# HLK-W806-KIT-V1_2.net
KiCad netlist of a schematic drawn in Altium Designer
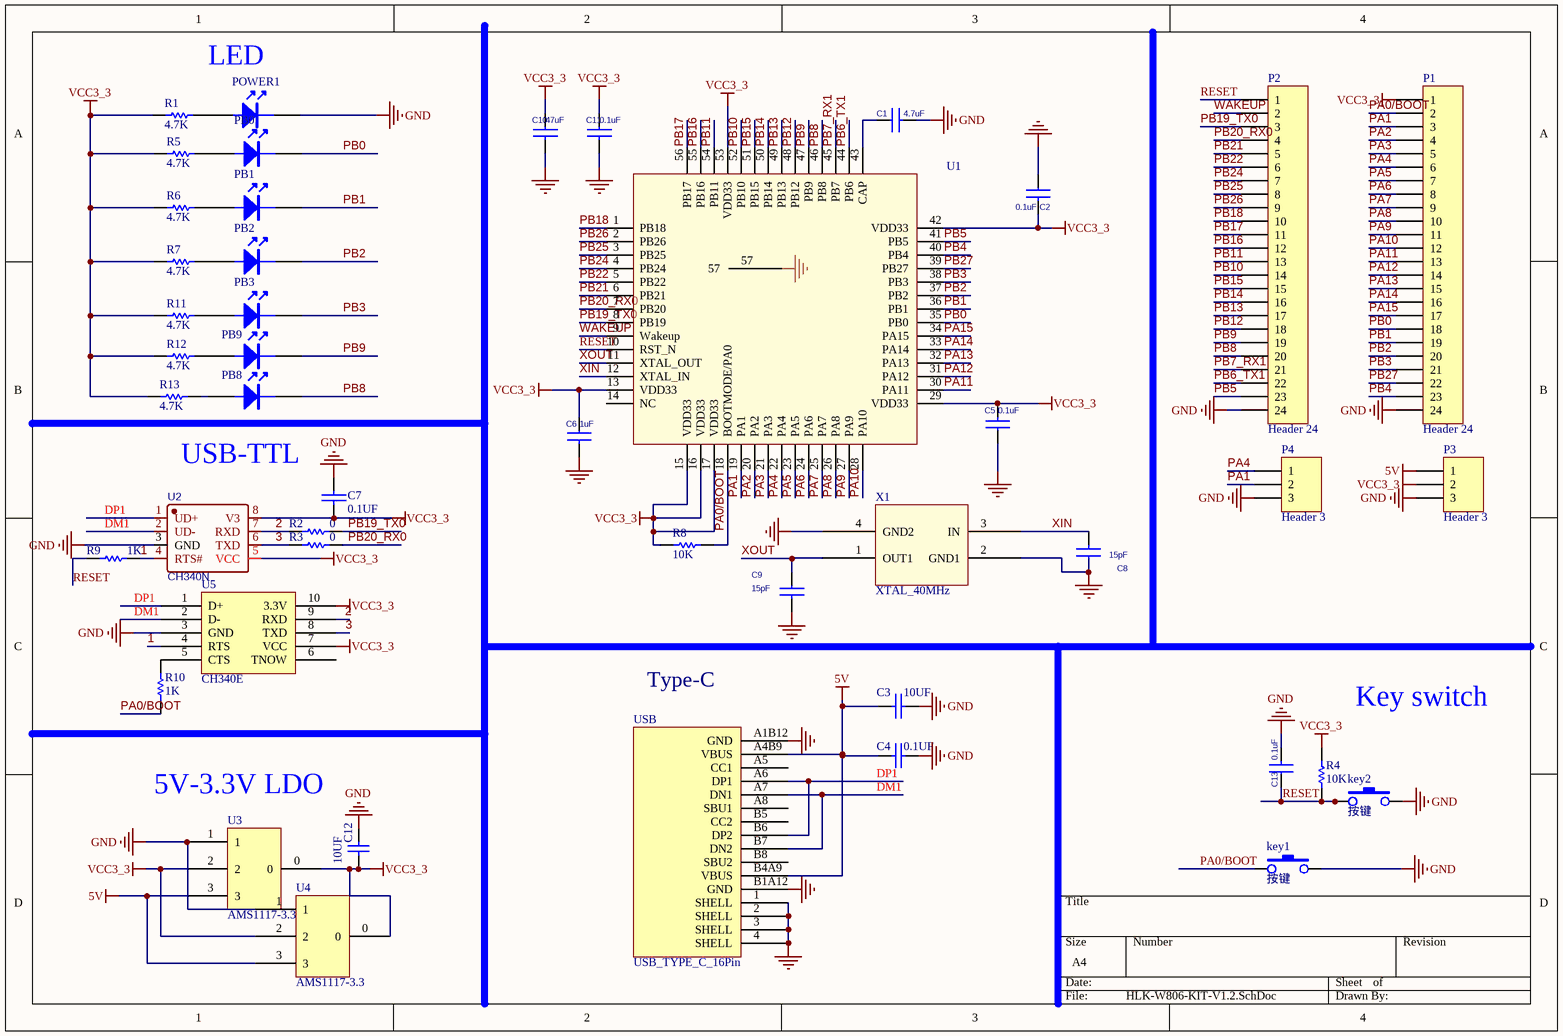
[diagram p0: HLK-W806-KIT-V1.2.SchDoc]

(export (version "E")
  (design (tool "Eeschema 10.0.6"))
  (components
    (comp (ref "C1") (value "4.7uF") (footprint "0603") (libsource (lib "*") (part "CAP NP_Dup1")))
    (comp (ref "C2") (value "0.1uF") (footprint "0603") (libsource (lib "*") (part "CAP NP_Dup1")))
    (comp (ref "C3")
      (value "10UF")
      (footprint "0603_1")
      (description "Capacitor")
      (libsource (lib "*") (part "CAP"))
    )
    (comp (ref "C4")
      (value "0.1UF")
      (footprint "0603_1")
      (description "Capacitor")
      (libsource (lib "*") (part "CAP"))
    )
    (comp (ref "C5") (value "0.1uF") (footprint "0603") (libsource (lib "*") (part "CAP NP_Dup1")))
    (comp (ref "C6") (value "1uF") (footprint "0603") (libsource (lib "*") (part "CAP NP_Dup1")))
    (comp (ref "C7")
      (value "0.1UF")
      (footprint "0603_1")
      (description "Capacitor")
      (libsource (lib "*") (part "CAP"))
    )
    (comp (ref "C8") (value "15pF") (footprint "0603") (libsource (lib "*") (part "CAP NP_Dup1")))
    (comp (ref "C9") (value "15pF") (footprint "0603") (libsource (lib "*") (part "CAP NP_Dup1")))
    (comp (ref "C10") (value "47uF") (footprint "R0805") (libsource (lib "*") (part "CAP NP_Dup1")))
    (comp (ref "C11") (value "0.1uF") (footprint "0603") (libsource (lib "*") (part "CAP NP_Dup1")))
    (comp (ref "C12")
      (value "10UF")
      (footprint "0603_1")
      (description "Capacitor")
      (fields (field (name "PUBLISHER") "Altium Limited"))
      (libsource (lib "Miscellaneous Devices") (part "Cap"))
    )
    (comp (ref "C13") (value "0.1uF") (footprint "0603") (libsource (lib "*") (part "CAP NP_Dup1")))
    (comp (ref "key1") (value "按键") (footprint "正按小龟") (libsource (lib "标准通用原理图库") (part "按键")))
    (comp (ref "key2") (value "按键") (footprint "正按小龟") (libsource (lib "标准通用原理图库") (part "按键")))
    (comp (ref "P1")
      (value "Header 24")
      (footprint "HDR1X24")
      (description "Header, 24-Pin")
      (fields (field (name "PUBLISHER") "Altium Limited"))
      (libsource (lib "Miscellaneous Connectors") (part "Header 24"))
    )
    (comp (ref "P2")
      (value "Header 24")
      (footprint "HDR1X24")
      (description "Header, 24-Pin")
      (fields (field (name "PUBLISHER") "Altium Limited"))
      (libsource (lib "Miscellaneous Connectors") (part "Header 24"))
    )
    (comp (ref "P3")
      (value "Header 3")
      (footprint "HDR1X3")
      (description "Header, 3-Pin")
      (fields (field (name "PUBLISHER") "Altium Limited"))
      (libsource (lib "Miscellaneous Connectors") (part "Header 3"))
    )
    (comp (ref "P4")
      (value "Header 3")
      (footprint "HDR1X3")
      (description "Header, 3-Pin")
      (fields (field (name "PUBLISHER") "Altium Limited"))
      (libsource (lib "Miscellaneous Connectors") (part "Header 3"))
    )
    (comp (ref "PB0")
      (value "~")
      (footprint "0603LED")
      (libsource (lib "Miscellaneous Devices") (part "LED"))
    )
    (comp (ref "PB1")
      (value "~")
      (footprint "0603LED")
      (libsource (lib "Miscellaneous Devices") (part "LED"))
    )
    (comp (ref "PB2")
      (value "~")
      (footprint "0603LED")
      (libsource (lib "Miscellaneous Devices") (part "LED"))
    )
    (comp (ref "PB3")
      (value "~")
      (footprint "0603LED")
      (libsource (lib "Miscellaneous Devices") (part "LED"))
    )
    (comp (ref "PB8")
      (value "~")
      (footprint "0603LED")
      (libsource (lib "Miscellaneous Devices") (part "LED"))
    )
    (comp (ref "PB9")
      (value "~")
      (footprint "0603LED")
      (libsource (lib "Miscellaneous Devices") (part "LED"))
    )
    (comp (ref "POWER1")
      (value "~")
      (footprint "0603LED")
      (libsource (lib "Miscellaneous Devices") (part "LED"))
    )
    (comp (ref "R1")
      (value "4.7K")
      (footprint "0603_1")
      (description "Resistor")
      (fields (field (name "PUBLISHER") "Altium Limited"))
      (libsource (lib "Miscellaneous Devices") (part "Res1"))
    )
    (comp (ref "R2")
      (value "0")
      (footprint "0603_1")
      (description "Resistor")
      (fields (field (name "PUBLISHER") "Altium Limited"))
      (libsource (lib "Miscellaneous Devices") (part "Res1"))
    )
    (comp (ref "R3")
      (value "0")
      (footprint "0603_1")
      (description "Resistor")
      (fields (field (name "PUBLISHER") "Altium Limited"))
      (libsource (lib "Miscellaneous Devices") (part "Res1"))
    )
    (comp (ref "R4")
      (value "10K")
      (footprint "0603_1")
      (description "Resistor")
      (fields (field (name "PUBLISHER") "Altium Limited"))
      (libsource (lib "Miscellaneous Devices") (part "Res1"))
    )
    (comp (ref "R5")
      (value "4.7K")
      (footprint "0603_1")
      (description "Resistor")
      (fields (field (name "PUBLISHER") "Altium Limited"))
      (libsource (lib "Miscellaneous Devices") (part "Res1"))
    )
    (comp (ref "R6")
      (value "4.7K")
      (footprint "0603_1")
      (description "Resistor")
      (fields (field (name "PUBLISHER") "Altium Limited"))
      (libsource (lib "Miscellaneous Devices") (part "Res1"))
    )
    (comp (ref "R7")
      (value "4.7K")
      (footprint "0603_1")
      (description "Resistor")
      (fields (field (name "PUBLISHER") "Altium Limited"))
      (libsource (lib "Miscellaneous Devices") (part "Res1"))
    )
    (comp (ref "R8")
      (value "10K")
      (footprint "0603_1")
      (description "Resistor")
      (fields (field (name "PUBLISHER") "Altium Limited"))
      (libsource (lib "Miscellaneous Devices") (part "Res1"))
    )
    (comp (ref "R9")
      (value "1K")
      (footprint "0603_1")
      (description "Resistor")
      (fields (field (name "PUBLISHER") "Altium Limited"))
      (libsource (lib "Miscellaneous Devices") (part "Res1"))
    )
    (comp (ref "R10")
      (value "1K")
      (footprint "R 0603_L")
      (description "Resistor")
      (fields (field (name "PUBLISHER") "Altium Limited"))
      (libsource (lib "Miscellaneous Devices") (part "Res1"))
    )
    (comp (ref "R11")
      (value "4.7K")
      (footprint "0603_1")
      (description "Resistor")
      (fields (field (name "PUBLISHER") "Altium Limited"))
      (libsource (lib "Miscellaneous Devices") (part "Res1"))
    )
    (comp (ref "R12")
      (value "4.7K")
      (footprint "0603_1")
      (description "Resistor")
      (fields (field (name "PUBLISHER") "Altium Limited"))
      (libsource (lib "Miscellaneous Devices") (part "Res1"))
    )
    (comp (ref "R13")
      (value "4.7K")
      (footprint "0603_1")
      (description "Resistor")
      (fields (field (name "PUBLISHER") "Altium Limited"))
      (libsource (lib "Miscellaneous Devices") (part "Res1"))
    )
    (comp (ref "U1")
      (value "Component_1")
      (footprint "QFN-56")
      (libsource (lib "Schlib") (part "Component_1"))
    )
    (comp (ref "U2")
      (value "CH340N")
      (footprint "SOP8")
      (fields (field (name "BOM_SUPPLIER PART") "C506813") (field (name "CONTRIBUTOR") "LCSC"))
      (libsource (lib "Schlib1") (part "CH340N"))
    )
    (comp (ref "U3")
      (value "AMS1117-3.3")
      (footprint "AMS1117")
      (libsource (lib "Schlib1") (part "Component_1"))
    )
    (comp (ref "U4")
      (value "AMS1117-3.3")
      (footprint "SOT223")
      (libsource (lib "Schlib1") (part "Component_1"))
    )
    (comp (ref "U5") (value "CH340E") (footprint "MSOP10_L") (libsource (lib "Schlib1") (part "CH340E")))
    (comp (ref "USB")
      (value "USB_TYPE_C_16Pin")
      (footprint "USB-C-16PIN-1")
      (libsource (lib "Interface") (part "USB_TYPE_C_16Pin"))
    )
    (comp (ref "X1")
      (value "XTAL_40MHz")
      (footprint "SMD-3225")
      (libsource (lib "Schlib1") (part "XTAL_40MHz"))
    )
  )
  (nets
    (net (code "1") (name "/1") (class "Default")
      (node (ref "R9") (pin "2") (pinfunction "2_2") (pintype "passive"))
      (node (ref "U2") (pin "4") (pinfunction "RTS#_4") (pintype "passive"))
      (node (ref "U5") (pin "4") (pinfunction "RTS_4") (pintype "passive"))
    )
    (net (code "2") (name "/2") (class "Default")
      (node (ref "R2") (pin "1") (pinfunction "1_1") (pintype "passive"))
      (node (ref "U2") (pin "7") (pinfunction "RXD_7") (pintype "passive"))
      (node (ref "U5") (pin "9") (pinfunction "RXD_9") (pintype "passive"))
    )
    (net (code "3") (name "/3") (class "Default")
      (node (ref "R3") (pin "1") (pinfunction "1_1") (pintype "passive"))
      (node (ref "U2") (pin "6") (pinfunction "TXD_6") (pintype "passive"))
      (node (ref "U5") (pin "8") (pinfunction "TXD_8") (pintype "passive"))
    )
    (net (code "4") (name "/DM1") (class "Default")
      (node (ref "U2") (pin "2") (pinfunction "UD-_2") (pintype "passive"))
      (node (ref "U5") (pin "2") (pinfunction "D-_2") (pintype "passive"))
      (node (ref "USB") (pin "A7") (pinfunction "DN1_A7") (pintype "passive"))
      (node (ref "USB") (pin "B7") (pinfunction "DN2_B7") (pintype "passive"))
    )
    (net (code "5") (name "/DP1") (class "Default")
      (node (ref "U2") (pin "1") (pinfunction "UD+_1") (pintype "passive"))
      (node (ref "U5") (pin "1") (pinfunction "D+_1") (pintype "passive"))
      (node (ref "USB") (pin "A6") (pinfunction "DP1_A6") (pintype "passive"))
      (node (ref "USB") (pin "B6") (pinfunction "DP2_B6") (pintype "passive"))
    )
    (net (code "6") (name "/PA0{slash}BOOT") (class "Default")
      (node (ref "P1") (pin "2") (pinfunction "2_2") (pintype "passive"))
      (node (ref "R10") (pin "1") (pinfunction "1_1") (pintype "passive"))
      (node (ref "R8") (pin "2") (pinfunction "2_2") (pintype "passive"))
      (node (ref "U1") (pin "18") (pinfunction "BOOTMODE/PA0_18") (pintype "passive"))
      (node (ref "key1") (pin "1") (pinfunction "1_1") (pintype "passive"))
    )
    (net (code "7") (name "/PA1") (class "Default")
      (node (ref "P1") (pin "3") (pinfunction "3_3") (pintype "passive"))
      (node (ref "P4") (pin "2") (pinfunction "2_2") (pintype "passive"))
      (node (ref "U1") (pin "19") (pinfunction "PA1_19") (pintype "passive"))
    )
    (net (code "8") (name "/PA2") (class "Default")
      (node (ref "P1") (pin "4") (pinfunction "4_4") (pintype "passive"))
      (node (ref "U1") (pin "20") (pinfunction "PA2_20") (pintype "passive"))
    )
    (net (code "9") (name "/PA3") (class "Default")
      (node (ref "P1") (pin "5") (pinfunction "5_5") (pintype "passive"))
      (node (ref "U1") (pin "21") (pinfunction "PA3_21") (pintype "passive"))
    )
    (net (code "10") (name "/PA4") (class "Default")
      (node (ref "P1") (pin "6") (pinfunction "6_6") (pintype "passive"))
      (node (ref "P4") (pin "1") (pinfunction "1_1") (pintype "passive"))
      (node (ref "U1") (pin "22") (pinfunction "PA4_22") (pintype "passive"))
    )
    (net (code "11") (name "/PA5") (class "Default")
      (node (ref "P1") (pin "7") (pinfunction "7_7") (pintype "passive"))
      (node (ref "U1") (pin "23") (pinfunction "PA5_23") (pintype "passive"))
    )
    (net (code "12") (name "/PA6") (class "Default")
      (node (ref "P1") (pin "8") (pinfunction "8_8") (pintype "passive"))
      (node (ref "U1") (pin "24") (pinfunction "PA6_24") (pintype "passive"))
    )
    (net (code "13") (name "/PA7") (class "Default")
      (node (ref "P1") (pin "9") (pinfunction "9_9") (pintype "passive"))
      (node (ref "U1") (pin "25") (pinfunction "PA7_25") (pintype "passive"))
    )
    (net (code "14") (name "/PA8") (class "Default")
      (node (ref "P1") (pin "10") (pinfunction "10_10") (pintype "passive"))
      (node (ref "U1") (pin "26") (pinfunction "PA8_26") (pintype "passive"))
    )
    (net (code "15") (name "/PA9") (class "Default")
      (node (ref "P1") (pin "11") (pinfunction "11_11") (pintype "passive"))
      (node (ref "U1") (pin "27") (pinfunction "PA9_27") (pintype "passive"))
    )
    (net (code "16") (name "/PA10") (class "Default")
      (node (ref "P1") (pin "12") (pinfunction "12_12") (pintype "passive"))
      (node (ref "U1") (pin "28") (pinfunction "PA10_28") (pintype "passive"))
    )
    (net (code "17") (name "/PA11") (class "Default")
      (node (ref "P1") (pin "13") (pinfunction "13_13") (pintype "passive"))
      (node (ref "U1") (pin "30") (pinfunction "PA11_30") (pintype "passive"))
    )
    (net (code "18") (name "/PA12") (class "Default")
      (node (ref "P1") (pin "14") (pinfunction "14_14") (pintype "passive"))
      (node (ref "U1") (pin "31") (pinfunction "PA12_31") (pintype "passive"))
    )
    (net (code "19") (name "/PA13") (class "Default")
      (node (ref "P1") (pin "15") (pinfunction "15_15") (pintype "passive"))
      (node (ref "U1") (pin "32") (pinfunction "PA13_32") (pintype "passive"))
    )
    (net (code "20") (name "/PA14") (class "Default")
      (node (ref "P1") (pin "16") (pinfunction "16_16") (pintype "passive"))
      (node (ref "U1") (pin "33") (pinfunction "PA14_33") (pintype "passive"))
    )
    (net (code "21") (name "/PA15") (class "Default")
      (node (ref "P1") (pin "17") (pinfunction "17_17") (pintype "passive"))
      (node (ref "U1") (pin "34") (pinfunction "PA15_34") (pintype "passive"))
    )
    (net (code "22") (name "/PB0") (class "Default")
      (node (ref "P1") (pin "18") (pinfunction "18_18") (pintype "passive"))
      (node (ref "PB0") (pin "2") (pinfunction "2_2") (pintype "passive"))
      (node (ref "U1") (pin "35") (pinfunction "PB0_35") (pintype "passive"))
    )
    (net (code "23") (name "/PB1") (class "Default")
      (node (ref "P1") (pin "19") (pinfunction "19_19") (pintype "passive"))
      (node (ref "PB1") (pin "2") (pinfunction "2_2") (pintype "passive"))
      (node (ref "U1") (pin "36") (pinfunction "PB1_36") (pintype "passive"))
    )
    (net (code "24") (name "/PB2") (class "Default")
      (node (ref "P1") (pin "20") (pinfunction "20_20") (pintype "passive"))
      (node (ref "PB2") (pin "2") (pinfunction "2_2") (pintype "passive"))
      (node (ref "U1") (pin "37") (pinfunction "PB2_37") (pintype "passive"))
    )
    (net (code "25") (name "/PB3") (class "Default")
      (node (ref "P1") (pin "21") (pinfunction "21_21") (pintype "passive"))
      (node (ref "PB3") (pin "2") (pinfunction "2_2") (pintype "passive"))
      (node (ref "U1") (pin "38") (pinfunction "PB3_38") (pintype "passive"))
    )
    (net (code "26") (name "/PB4") (class "Default")
      (node (ref "P1") (pin "23") (pinfunction "23_23") (pintype "passive"))
      (node (ref "U1") (pin "40") (pinfunction "PB4_40") (pintype "passive"))
    )
    (net (code "27") (name "/PB5") (class "Default")
      (node (ref "P2") (pin "23") (pinfunction "23_23") (pintype "passive"))
      (node (ref "U1") (pin "41") (pinfunction "PB5_41") (pintype "passive"))
    )
    (net (code "28") (name "/PB6_TX1") (class "Default")
      (node (ref "P2") (pin "22") (pinfunction "22_22") (pintype "passive"))
      (node (ref "U1") (pin "44") (pinfunction "PB6_44") (pintype "passive"))
    )
    (net (code "29") (name "/PB7_RX1") (class "Default")
      (node (ref "P2") (pin "21") (pinfunction "21_21") (pintype "passive"))
      (node (ref "U1") (pin "45") (pinfunction "PB7_45") (pintype "passive"))
    )
    (net (code "30") (name "/PB8") (class "Default")
      (node (ref "P2") (pin "20") (pinfunction "20_20") (pintype "passive"))
      (node (ref "PB8") (pin "2") (pinfunction "2_2") (pintype "passive"))
      (node (ref "U1") (pin "46") (pinfunction "PB8_46") (pintype "passive"))
    )
    (net (code "31") (name "/PB9") (class "Default")
      (node (ref "P2") (pin "19") (pinfunction "19_19") (pintype "passive"))
      (node (ref "PB9") (pin "2") (pinfunction "2_2") (pintype "passive"))
      (node (ref "U1") (pin "47") (pinfunction "PB9_47") (pintype "passive"))
    )
    (net (code "32") (name "/PB10") (class "Default")
      (node (ref "P2") (pin "14") (pinfunction "14_14") (pintype "passive"))
      (node (ref "U1") (pin "52") (pinfunction "PB10_52") (pintype "passive"))
    )
    (net (code "33") (name "/PB11") (class "Default")
      (node (ref "P2") (pin "13") (pinfunction "13_13") (pintype "passive"))
      (node (ref "U1") (pin "54") (pinfunction "PB11_54") (pintype "passive"))
    )
    (net (code "34") (name "/PB12") (class "Default")
      (node (ref "P2") (pin "18") (pinfunction "18_18") (pintype "passive"))
      (node (ref "U1") (pin "48") (pinfunction "PB12_48") (pintype "passive"))
    )
    (net (code "35") (name "/PB13") (class "Default")
      (node (ref "P2") (pin "17") (pinfunction "17_17") (pintype "passive"))
      (node (ref "U1") (pin "49") (pinfunction "PB13_49") (pintype "passive"))
    )
    (net (code "36") (name "/PB14") (class "Default")
      (node (ref "P2") (pin "16") (pinfunction "16_16") (pintype "passive"))
      (node (ref "U1") (pin "50") (pinfunction "PB14_50") (pintype "passive"))
    )
    (net (code "37") (name "/PB15") (class "Default")
      (node (ref "P2") (pin "15") (pinfunction "15_15") (pintype "passive"))
      (node (ref "U1") (pin "51") (pinfunction "PB15_51") (pintype "passive"))
    )
    (net (code "38") (name "/PB16") (class "Default")
      (node (ref "P2") (pin "12") (pinfunction "12_12") (pintype "passive"))
      (node (ref "U1") (pin "55") (pinfunction "PB16_55") (pintype "passive"))
    )
    (net (code "39") (name "/PB17") (class "Default")
      (node (ref "P2") (pin "11") (pinfunction "11_11") (pintype "passive"))
      (node (ref "U1") (pin "56") (pinfunction "PB17_56") (pintype "passive"))
    )
    (net (code "40") (name "/PB18") (class "Default")
      (node (ref "P2") (pin "10") (pinfunction "10_10") (pintype "passive"))
      (node (ref "U1") (pin "1") (pinfunction "PB18_1") (pintype "passive"))
    )
    (net (code "41") (name "/PB19_TX0") (class "Default")
      (node (ref "P2") (pin "3") (pinfunction "3_3") (pintype "passive"))
      (node (ref "R2") (pin "2") (pinfunction "2_2") (pintype "passive"))
      (node (ref "U1") (pin "8") (pinfunction "PB19_8") (pintype "passive"))
    )
    (net (code "42") (name "/PB20_RX0") (class "Default")
      (node (ref "P2") (pin "4") (pinfunction "4_4") (pintype "passive"))
      (node (ref "R3") (pin "2") (pinfunction "2_2") (pintype "passive"))
      (node (ref "U1") (pin "7") (pinfunction "PB20_7") (pintype "passive"))
    )
    (net (code "43") (name "/PB21") (class "Default")
      (node (ref "P2") (pin "5") (pinfunction "5_5") (pintype "passive"))
      (node (ref "U1") (pin "6") (pinfunction "PB21_6") (pintype "passive"))
    )
    (net (code "44") (name "/PB22") (class "Default")
      (node (ref "P2") (pin "6") (pinfunction "6_6") (pintype "passive"))
      (node (ref "U1") (pin "5") (pinfunction "PB22_5") (pintype "passive"))
    )
    (net (code "45") (name "/PB24") (class "Default")
      (node (ref "P2") (pin "7") (pinfunction "7_7") (pintype "passive"))
      (node (ref "U1") (pin "4") (pinfunction "PB24_4") (pintype "passive"))
    )
    (net (code "46") (name "/PB25") (class "Default")
      (node (ref "P2") (pin "8") (pinfunction "8_8") (pintype "passive"))
      (node (ref "U1") (pin "3") (pinfunction "PB25_3") (pintype "passive"))
    )
    (net (code "47") (name "/PB26") (class "Default")
      (node (ref "P2") (pin "9") (pinfunction "9_9") (pintype "passive"))
      (node (ref "U1") (pin "2") (pinfunction "PB26_2") (pintype "passive"))
    )
    (net (code "48") (name "/PB27") (class "Default")
      (node (ref "P1") (pin "22") (pinfunction "22_22") (pintype "passive"))
      (node (ref "U1") (pin "39") (pinfunction "PB27_39") (pintype "passive"))
    )
    (net (code "49") (name "/RESET") (class "Default")
      (node (ref "C13") (pin "1") (pinfunction "1_1") (pintype "passive"))
      (node (ref "P2") (pin "1") (pinfunction "1_1") (pintype "passive"))
      (node (ref "R4") (pin "1") (pinfunction "1_1") (pintype "passive"))
      (node (ref "R9") (pin "1") (pinfunction "1_1") (pintype "passive"))
      (node (ref "U1") (pin "10") (pinfunction "RST_N_10") (pintype "passive"))
      (node (ref "key2") (pin "1") (pinfunction "1_1") (pintype "passive"))
    )
    (net (code "50") (name "/WAKEUP") (class "Default")
      (node (ref "P2") (pin "2") (pinfunction "2_2") (pintype "passive"))
      (node (ref "U1") (pin "9") (pinfunction "Wakeup_9") (pintype "passive"))
    )
    (net (code "51") (name "/XIN") (class "Default")
      (node (ref "C8") (pin "2") (pinfunction "2_2") (pintype "passive"))
      (node (ref "U1") (pin "12") (pinfunction "XTAL_IN_12") (pintype "passive"))
      (node (ref "X1") (pin "3") (pinfunction "IN_3") (pintype "passive"))
    )
    (net (code "52") (name "/XOUT") (class "Default")
      (node (ref "C9") (pin "1") (pinfunction "1_1") (pintype "passive"))
      (node (ref "U1") (pin "11") (pinfunction "XTAL_OUT_11") (pintype "passive"))
      (node (ref "X1") (pin "1") (pinfunction "OUT1_1") (pintype "passive"))
    )
    (net (code "53") (name "5V") (class "Default")
      (node (ref "C3") (pin "2") (pinfunction "2_2") (pintype "passive"))
      (node (ref "C4") (pin "2") (pinfunction "2_2") (pintype "passive"))
      (node (ref "P3") (pin "1") (pinfunction "1_1") (pintype "passive"))
      (node (ref "U3") (pin "3") (pinfunction "3_3") (pintype "passive"))
      (node (ref "U4") (pin "3") (pinfunction "3_3") (pintype "passive"))
      (node (ref "USB") (pin "A4B9") (pinfunction "VBUS_A4B9") (pintype "passive"))
      (node (ref "USB") (pin "B4A9") (pinfunction "VBUS_B4A9") (pintype "passive"))
    )
    (net (code "54") (name "GND") (class "Default")
      (node (ref "C1") (pin "2") (pinfunction "2_2") (pintype "passive"))
      (node (ref "C10") (pin "2") (pinfunction "2_2") (pintype "passive"))
      (node (ref "C11") (pin "2") (pinfunction "2_2") (pintype "passive"))
      (node (ref "C12") (pin "1") (pinfunction "1_1") (pintype "passive"))
      (node (ref "C13") (pin "2") (pinfunction "2_2") (pintype "passive"))
      (node (ref "C2") (pin "1") (pinfunction "1_1") (pintype "passive"))
      (node (ref "C3") (pin "1") (pinfunction "1_1") (pintype "passive"))
      (node (ref "C4") (pin "1") (pinfunction "1_1") (pintype "passive"))
      (node (ref "C5") (pin "1") (pinfunction "1_1") (pintype "passive"))
      (node (ref "C6") (pin "2") (pinfunction "2_2") (pintype "passive"))
      (node (ref "C7") (pin "1") (pinfunction "1_1") (pintype "passive"))
      (node (ref "C8") (pin "1") (pinfunction "1_1") (pintype "passive"))
      (node (ref "C9") (pin "2") (pinfunction "2_2") (pintype "passive"))
      (node (ref "P1") (pin "24") (pinfunction "24_24") (pintype "passive"))
      (node (ref "P2") (pin "24") (pinfunction "24_24") (pintype "passive"))
      (node (ref "P3") (pin "3") (pinfunction "3_3") (pintype "passive"))
      (node (ref "P4") (pin "3") (pinfunction "3_3") (pintype "passive"))
      (node (ref "POWER1") (pin "2") (pinfunction "2_2") (pintype "passive"))
      (node (ref "U1") (pin "57") (pinfunction "57_57") (pintype "passive"))
      (node (ref "U2") (pin "3") (pinfunction "GND_3") (pintype "passive"))
      (node (ref "U3") (pin "1") (pinfunction "1_1") (pintype "passive"))
      (node (ref "U4") (pin "1") (pinfunction "1_1") (pintype "passive"))
      (node (ref "U5") (pin "3") (pinfunction "GND_3") (pintype "passive"))
      (node (ref "USB") (pin "1") (pinfunction "SHELL_1") (pintype "passive"))
      (node (ref "USB") (pin "2") (pinfunction "SHELL_2") (pintype "passive"))
      (node (ref "USB") (pin "3") (pinfunction "SHELL_3") (pintype "passive"))
      (node (ref "USB") (pin "4") (pinfunction "SHELL_4") (pintype "passive"))
      (node (ref "USB") (pin "A1B12") (pinfunction "GND_A1B12") (pintype "passive"))
      (node (ref "USB") (pin "B1A12") (pinfunction "GND_B1A12") (pintype "passive"))
      (node (ref "X1") (pin "2") (pinfunction "GND1_2") (pintype "passive"))
      (node (ref "X1") (pin "4") (pinfunction "GND2_4") (pintype "passive"))
      (node (ref "key1") (pin "2") (pinfunction "2_2") (pintype "passive"))
      (node (ref "key2") (pin "2") (pinfunction "2_2") (pintype "passive"))
    )
    (net (code "55") (name "Net-(PB0-Pad1)") (class "Default")
      (node (ref "PB0") (pin "1") (pinfunction "1_1") (pintype "passive"))
      (node (ref "R5") (pin "2") (pinfunction "2_2") (pintype "passive"))
    )
    (net (code "56") (name "Net-(PB1-Pad1)") (class "Default")
      (node (ref "PB1") (pin "1") (pinfunction "1_1") (pintype "passive"))
      (node (ref "R6") (pin "2") (pinfunction "2_2") (pintype "passive"))
    )
    (net (code "57") (name "Net-(PB2-Pad1)") (class "Default")
      (node (ref "PB2") (pin "1") (pinfunction "1_1") (pintype "passive"))
      (node (ref "R7") (pin "2") (pinfunction "2_2") (pintype "passive"))
    )
    (net (code "58") (name "Net-(PB3-Pad1)") (class "Default")
      (node (ref "PB3") (pin "1") (pinfunction "1_1") (pintype "passive"))
      (node (ref "R11") (pin "2") (pinfunction "2_2") (pintype "passive"))
    )
    (net (code "59") (name "Net-(PB8-Pad1)") (class "Default")
      (node (ref "PB8") (pin "1") (pinfunction "1_1") (pintype "passive"))
      (node (ref "R13") (pin "2") (pinfunction "2_2") (pintype "passive"))
    )
    (net (code "60") (name "Net-(PB9-Pad1)") (class "Default")
      (node (ref "PB9") (pin "1") (pinfunction "1_1") (pintype "passive"))
      (node (ref "R12") (pin "2") (pinfunction "2_2") (pintype "passive"))
    )
    (net (code "61") (name "Net-(POWER1-Pad1)") (class "Default")
      (node (ref "POWER1") (pin "1") (pinfunction "1_1") (pintype "passive"))
      (node (ref "R1") (pin "2") (pinfunction "2_2") (pintype "passive"))
    )
    (net (code "62") (name "Net-(U1-CAP)") (class "Default")
      (node (ref "C1") (pin "1") (pinfunction "1_1") (pintype "passive"))
      (node (ref "U1") (pin "43") (pinfunction "CAP_43") (pintype "passive"))
    )
    (net (code "63") (name "Net-(U5-CTS)") (class "Default")
      (node (ref "R10") (pin "2") (pinfunction "2_2") (pintype "passive"))
      (node (ref "U5") (pin "5") (pinfunction "CTS_5") (pintype "passive"))
    )
    (net (code "64") (name "VCC3_3") (class "Default")
      (node (ref "C10") (pin "1") (pinfunction "1_1") (pintype "passive"))
      (node (ref "C11") (pin "1") (pinfunction "1_1") (pintype "passive"))
      (node (ref "C12") (pin "2") (pinfunction "2_2") (pintype "passive"))
      (node (ref "C2") (pin "2") (pinfunction "2_2") (pintype "passive"))
      (node (ref "C5") (pin "2") (pinfunction "2_2") (pintype "passive"))
      (node (ref "C6") (pin "1") (pinfunction "1_1") (pintype "passive"))
      (node (ref "C7") (pin "2") (pinfunction "2_2") (pintype "passive"))
      (node (ref "P1") (pin "1") (pinfunction "1_1") (pintype "passive"))
      (node (ref "P3") (pin "2") (pinfunction "2_2") (pintype "passive"))
      (node (ref "R1") (pin "1") (pinfunction "1_1") (pintype "passive"))
      (node (ref "R11") (pin "1") (pinfunction "1_1") (pintype "passive"))
      (node (ref "R12") (pin "1") (pinfunction "1_1") (pintype "passive"))
      (node (ref "R13") (pin "1") (pinfunction "1_1") (pintype "passive"))
      (node (ref "R4") (pin "2") (pinfunction "2_2") (pintype "passive"))
      (node (ref "R5") (pin "1") (pinfunction "1_1") (pintype "passive"))
      (node (ref "R6") (pin "1") (pinfunction "1_1") (pintype "passive"))
      (node (ref "R7") (pin "1") (pinfunction "1_1") (pintype "passive"))
      (node (ref "R8") (pin "1") (pinfunction "1_1") (pintype "passive"))
      (node (ref "U1") (pin "13") (pinfunction "VDD33_13") (pintype "passive"))
      (node (ref "U1") (pin "15") (pinfunction "VDD33_15") (pintype "passive"))
      (node (ref "U1") (pin "16") (pinfunction "VDD33_16") (pintype "passive"))
      (node (ref "U1") (pin "17") (pinfunction "VDD33_17") (pintype "passive"))
      (node (ref "U1") (pin "29") (pinfunction "VDD33_29") (pintype "passive"))
      (node (ref "U1") (pin "42") (pinfunction "VDD33_42") (pintype "passive"))
      (node (ref "U1") (pin "53") (pinfunction "VDD33_53") (pintype "passive"))
      (node (ref "U2") (pin "5") (pinfunction "VCC_5") (pintype "passive"))
      (node (ref "U2") (pin "8") (pinfunction "V3_8") (pintype "passive"))
      (node (ref "U3") (pin "0") (pinfunction "0_0") (pintype "passive"))
      (node (ref "U3") (pin "2") (pinfunction "2_2") (pintype "passive"))
      (node (ref "U4") (pin "0") (pinfunction "0_0") (pintype "passive"))
      (node (ref "U4") (pin "2") (pinfunction "2_2") (pintype "passive"))
      (node (ref "U5") (pin "10") (pinfunction "3.3V_10") (pintype "passive"))
      (node (ref "U5") (pin "7") (pinfunction "VCC_7") (pintype "passive"))
    )
    (net (code "65") (name "unconnected-(U1-NC-Pad14)") (class "Default")
      (node (ref "U1") (pin "14") (pinfunction "NC_14") (pintype "passive"))
    )
    (net (code "66") (name "unconnected-(U5-TNOW-Pad6)") (class "Default")
      (node (ref "U5") (pin "6") (pinfunction "TNOW_6") (pintype "passive"))
    )
    (net (code "67") (name "unconnected-(USB-CC1-PadA5)") (class "Default")
      (node (ref "USB") (pin "A5") (pinfunction "CC1_A5") (pintype "passive"))
    )
    (net (code "68") (name "unconnected-(USB-CC2-PadB5)") (class "Default")
      (node (ref "USB") (pin "B5") (pinfunction "CC2_B5") (pintype "passive"))
    )
    (net (code "69") (name "unconnected-(USB-SBU1-PadA8)") (class "Default")
      (node (ref "USB") (pin "A8") (pinfunction "SBU1_A8") (pintype "passive"))
    )
    (net (code "70") (name "unconnected-(USB-SBU2-PadB8)") (class "Default")
      (node (ref "USB") (pin "B8") (pinfunction "SBU2_B8") (pintype "passive"))
    )
  )
)
